# qstp_q1.net
KiCad netlist of a schematic drawn in EAGLE
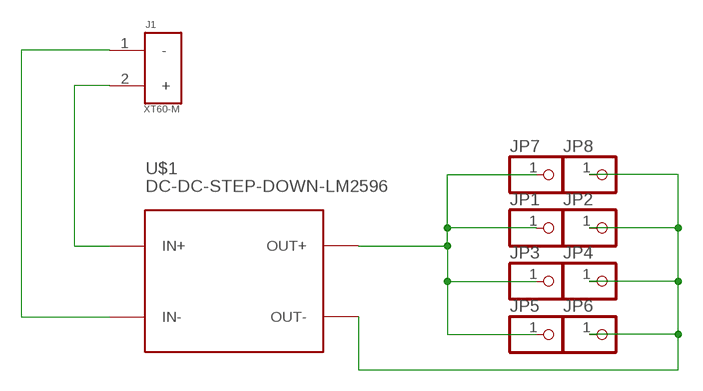
[diagram p0: schematic, sheet 1]

(export (version "E")
  (design (tool "Eeschema 10.0.6"))
  (components
    (comp (ref "J1")
      (value "XT60-M")
      (footprint "eagle-import:AMASS_XT60-M")
      (fields (field (name "MF") "AMASS"))
      (libsource (lib "eagle-import") (part "XT60-M"))
    )
    (comp (ref "JP1")
      (value "PINHD-1X1")
      (footprint "eagle-import:1X01")
      (libsource (lib "eagle-import") (part "PINHD-1X1"))
    )
    (comp (ref "JP2")
      (value "PINHD-1X1")
      (footprint "eagle-import:1X01")
      (libsource (lib "eagle-import") (part "PINHD-1X1"))
    )
    (comp (ref "JP3")
      (value "PINHD-1X1")
      (footprint "eagle-import:1X01")
      (libsource (lib "eagle-import") (part "PINHD-1X1"))
    )
    (comp (ref "JP4")
      (value "PINHD-1X1")
      (footprint "eagle-import:1X01")
      (libsource (lib "eagle-import") (part "PINHD-1X1"))
    )
    (comp (ref "JP5")
      (value "PINHD-1X1")
      (footprint "eagle-import:1X01")
      (libsource (lib "eagle-import") (part "PINHD-1X1"))
    )
    (comp (ref "JP6")
      (value "PINHD-1X1")
      (footprint "eagle-import:1X01")
      (libsource (lib "eagle-import") (part "PINHD-1X1"))
    )
    (comp (ref "JP7")
      (value "PINHD-1X1")
      (footprint "eagle-import:1X01")
      (libsource (lib "eagle-import") (part "PINHD-1X1"))
    )
    (comp (ref "JP8")
      (value "PINHD-1X1")
      (footprint "eagle-import:1X01")
      (libsource (lib "eagle-import") (part "PINHD-1X1"))
    )
    (comp (ref "U$1")
      (value "DC-DC-STEP-DOWN-LM2596")
      (footprint "eagle-import:DC-DC-STEP-DOWN-LM2596")
      (libsource (lib "eagle-import") (part "DC-DC-STEP-DOWN-LM2596"))
    )
  )
  (nets
    (net (code "1") (name "Net-(J1-+)") (class "Default")
      (node (ref "J1") (pin "2") (pinfunction "+_2") (pintype "passive"))
      (node (ref "U$1") (pin "IN+") (pinfunction "IN+_IN+") (pintype "bidirectional"))
    )
    (net (code "2") (name "Net-(J1--)") (class "Default")
      (node (ref "J1") (pin "1") (pinfunction "-_1") (pintype "passive"))
      (node (ref "U$1") (pin "IN-") (pinfunction "IN-_IN-") (pintype "bidirectional"))
    )
    (net (code "3") (name "Net-(JP1-Pad1)") (class "Default")
      (node (ref "JP1") (pin "1") (pinfunction "1_1") (pintype "passive"))
      (node (ref "JP3") (pin "1") (pinfunction "1_1") (pintype "passive"))
      (node (ref "JP5") (pin "1") (pinfunction "1_1") (pintype "passive"))
      (node (ref "JP7") (pin "1") (pinfunction "1_1") (pintype "passive"))
      (node (ref "U$1") (pin "OUT+") (pinfunction "OUT+_OUT+") (pintype "bidirectional"))
    )
    (net (code "4") (name "Net-(JP2-Pad1)") (class "Default")
      (node (ref "JP2") (pin "1") (pinfunction "1_1") (pintype "passive"))
      (node (ref "JP4") (pin "1") (pinfunction "1_1") (pintype "passive"))
      (node (ref "JP6") (pin "1") (pinfunction "1_1") (pintype "passive"))
      (node (ref "JP8") (pin "1") (pinfunction "1_1") (pintype "passive"))
      (node (ref "U$1") (pin "OUT-") (pinfunction "OUT-_OUT-") (pintype "bidirectional"))
    )
  )
)
